# Audio.net
KiCad netlist of a schematic drawn in Altium Designer
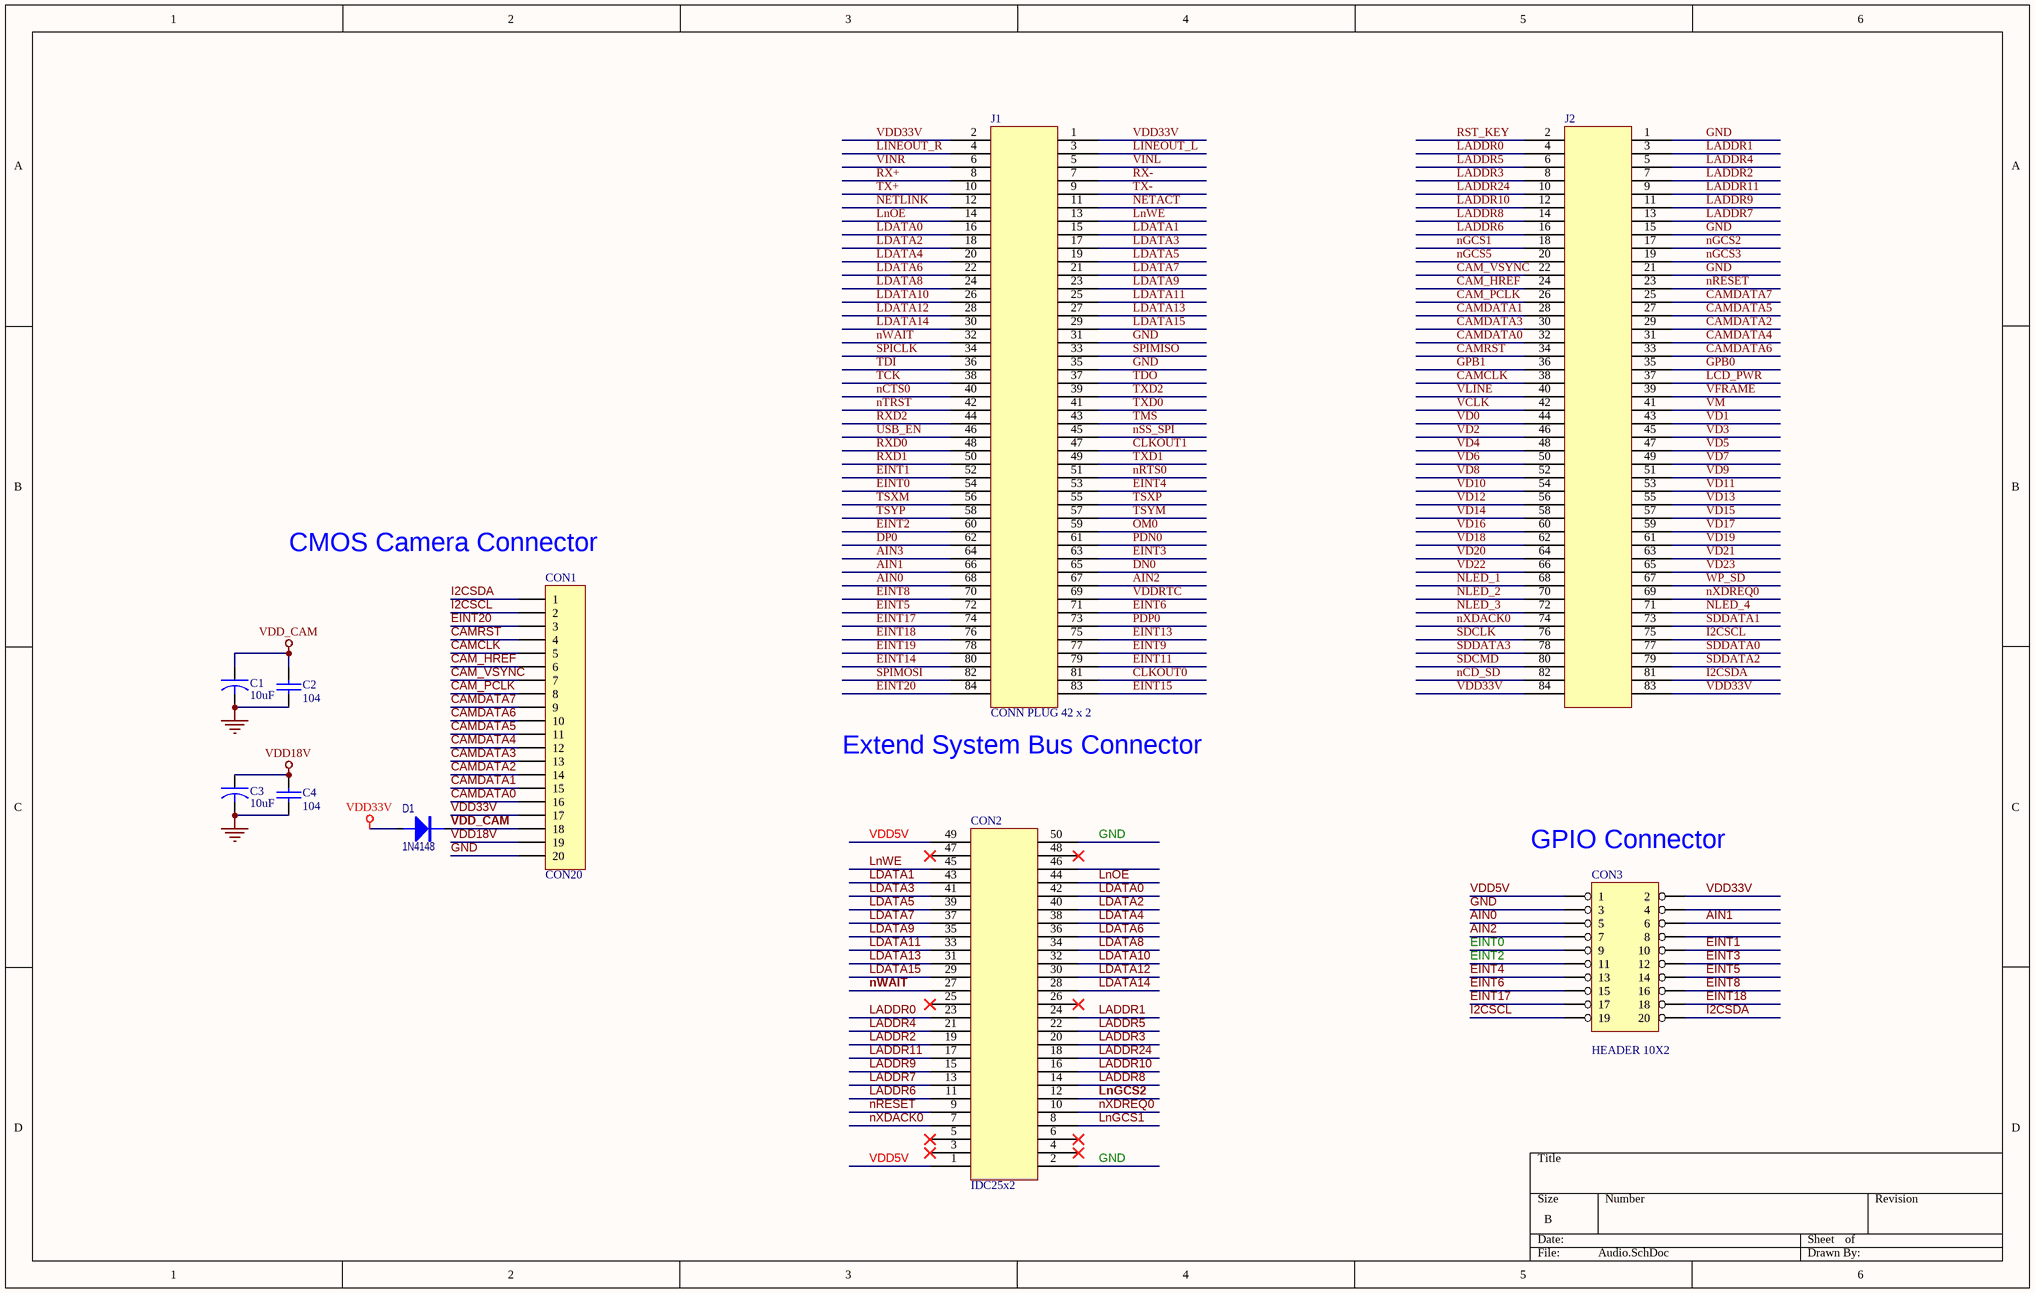
[diagram p0: Audio.SchDoc]

(export (version "E")
  (design (tool "Eeschema 10.0.6"))
  (components
    (comp (ref "C1")
      (value "10uF")
      (footprint "3216A")
      (description "Capacitor")
      (libsource (lib "*") (part "CAPACITOR"))
    )
    (comp (ref "C2")
      (value "104")
      (footprint "0603A")
      (description "Capacitor")
      (libsource (lib "*") (part "CAP"))
    )
    (comp (ref "C3")
      (value "10uF")
      (footprint "3216A")
      (description "Capacitor")
      (libsource (lib "*") (part "CAPACITOR"))
    )
    (comp (ref "C4")
      (value "104")
      (footprint "0603A")
      (description "Capacitor")
      (libsource (lib "*") (part "CAP"))
    )
    (comp (ref "CON1")
      (value "CON20")
      (footprint "IDC20SS")
      (description "Connector")
      (libsource (lib "*") (part "CON20"))
    )
    (comp (ref "CON2") (value "IDC25x2") (footprint "IDC25X2") (libsource (lib "Schlib1") (part "IDC25x2")))
    (comp (ref "CON3") (value "HEADER 10X2") (footprint "IDC20SS") (libsource (lib "*") (part "HEADER 10X2")))
    (comp (ref "D1") (value "1N4148") (footprint "D1206") (libsource (lib "*") (part "DIODE")))
    (comp (ref "J1")
      (value "CONN PLUG 42 x 2")
      (footprint "DIP84")
      (libsource (lib "*") (part "CONN PLUG 42 x 2"))
    )
    (comp (ref "J2")
      (value "CONN PLUG 42 x 2")
      (footprint "DIP84")
      (libsource (lib "*") (part "CONN PLUG 42 x 2"))
    )
  )
  (nets
    (net (code "1") (name "/AIN0") (class "Default")
      (node (ref "CON3") (pin "5") (pinfunction "5_5") (pintype "passive"))
      (node (ref "J1") (pin "68") (pinfunction "68_68") (pintype "passive"))
    )
    (net (code "2") (name "/AIN1") (class "Default")
      (node (ref "CON3") (pin "6") (pinfunction "6_6") (pintype "passive"))
      (node (ref "J1") (pin "66") (pinfunction "66_66") (pintype "passive"))
    )
    (net (code "3") (name "/AIN2") (class "Default")
      (node (ref "CON3") (pin "7") (pinfunction "7_7") (pintype "passive"))
      (node (ref "J1") (pin "67") (pinfunction "67_67") (pintype "passive"))
    )
    (net (code "4") (name "/AIN3") (class "Default")
      (node (ref "J1") (pin "64") (pinfunction "64_64") (pintype "passive"))
    )
    (net (code "5") (name "/CAMCLK") (class "Default")
      (node (ref "CON1") (pin "5") (pinfunction "5_5") (pintype "passive"))
      (node (ref "J2") (pin "38") (pinfunction "38_38") (pintype "passive"))
    )
    (net (code "6") (name "/CAMDATA0") (class "Default")
      (node (ref "CON1") (pin "16") (pinfunction "16_16") (pintype "passive"))
      (node (ref "J2") (pin "32") (pinfunction "32_32") (pintype "passive"))
    )
    (net (code "7") (name "/CAMDATA1") (class "Default")
      (node (ref "CON1") (pin "15") (pinfunction "15_15") (pintype "passive"))
      (node (ref "J2") (pin "28") (pinfunction "28_28") (pintype "passive"))
    )
    (net (code "8") (name "/CAMDATA2") (class "Default")
      (node (ref "CON1") (pin "14") (pinfunction "14_14") (pintype "passive"))
      (node (ref "J2") (pin "29") (pinfunction "29_29") (pintype "passive"))
    )
    (net (code "9") (name "/CAMDATA3") (class "Default")
      (node (ref "CON1") (pin "13") (pinfunction "13_13") (pintype "passive"))
      (node (ref "J2") (pin "30") (pinfunction "30_30") (pintype "passive"))
    )
    (net (code "10") (name "/CAMDATA4") (class "Default")
      (node (ref "CON1") (pin "12") (pinfunction "12_12") (pintype "passive"))
      (node (ref "J2") (pin "31") (pinfunction "31_31") (pintype "passive"))
    )
    (net (code "11") (name "/CAMDATA5") (class "Default")
      (node (ref "CON1") (pin "11") (pinfunction "11_11") (pintype "passive"))
      (node (ref "J2") (pin "27") (pinfunction "27_27") (pintype "passive"))
    )
    (net (code "12") (name "/CAMDATA6") (class "Default")
      (node (ref "CON1") (pin "10") (pinfunction "10_10") (pintype "passive"))
      (node (ref "J2") (pin "33") (pinfunction "33_33") (pintype "passive"))
    )
    (net (code "13") (name "/CAMDATA7") (class "Default")
      (node (ref "CON1") (pin "9") (pinfunction "9_9") (pintype "passive"))
      (node (ref "J2") (pin "25") (pinfunction "25_25") (pintype "passive"))
    )
    (net (code "14") (name "/CAMRST") (class "Default")
      (node (ref "CON1") (pin "4") (pinfunction "4_4") (pintype "passive"))
      (node (ref "J2") (pin "34") (pinfunction "34_34") (pintype "passive"))
    )
    (net (code "15") (name "/CAM_HREF") (class "Default")
      (node (ref "CON1") (pin "6") (pinfunction "6_6") (pintype "passive"))
      (node (ref "J2") (pin "24") (pinfunction "24_24") (pintype "passive"))
    )
    (net (code "16") (name "/CAM_PCLK") (class "Default")
      (node (ref "CON1") (pin "8") (pinfunction "8_8") (pintype "passive"))
      (node (ref "J2") (pin "26") (pinfunction "26_26") (pintype "passive"))
    )
    (net (code "17") (name "/CAM_VSYNC") (class "Default")
      (node (ref "CON1") (pin "7") (pinfunction "7_7") (pintype "passive"))
      (node (ref "J2") (pin "22") (pinfunction "22_22") (pintype "passive"))
    )
    (net (code "18") (name "/CLKOUT0") (class "Default")
      (node (ref "J1") (pin "81") (pinfunction "81_81") (pintype "passive"))
    )
    (net (code "19") (name "/CLKOUT1") (class "Default")
      (node (ref "J1") (pin "47") (pinfunction "47_47") (pintype "passive"))
    )
    (net (code "20") (name "/DN0") (class "Default")
      (node (ref "J1") (pin "65") (pinfunction "65_65") (pintype "passive"))
    )
    (net (code "21") (name "/DP0") (class "Default")
      (node (ref "J1") (pin "62") (pinfunction "62_62") (pintype "passive"))
    )
    (net (code "22") (name "/EINT0") (class "Default")
      (node (ref "CON3") (pin "9") (pinfunction "9_9") (pintype "passive"))
      (node (ref "J1") (pin "54") (pinfunction "54_54") (pintype "passive"))
    )
    (net (code "23") (name "/EINT1") (class "Default")
      (node (ref "CON3") (pin "10") (pinfunction "10_10") (pintype "passive"))
      (node (ref "J1") (pin "52") (pinfunction "52_52") (pintype "passive"))
    )
    (net (code "24") (name "/EINT2") (class "Default")
      (node (ref "CON3") (pin "11") (pinfunction "11_11") (pintype "passive"))
      (node (ref "J1") (pin "60") (pinfunction "60_60") (pintype "passive"))
    )
    (net (code "25") (name "/EINT3") (class "Default")
      (node (ref "CON3") (pin "12") (pinfunction "12_12") (pintype "passive"))
      (node (ref "J1") (pin "63") (pinfunction "63_63") (pintype "passive"))
    )
    (net (code "26") (name "/EINT4") (class "Default")
      (node (ref "CON3") (pin "13") (pinfunction "13_13") (pintype "passive"))
      (node (ref "J1") (pin "53") (pinfunction "53_53") (pintype "passive"))
    )
    (net (code "27") (name "/EINT5") (class "Default")
      (node (ref "CON3") (pin "14") (pinfunction "14_14") (pintype "passive"))
      (node (ref "J1") (pin "72") (pinfunction "72_72") (pintype "passive"))
    )
    (net (code "28") (name "/EINT6") (class "Default")
      (node (ref "CON3") (pin "15") (pinfunction "15_15") (pintype "passive"))
      (node (ref "J1") (pin "71") (pinfunction "71_71") (pintype "passive"))
    )
    (net (code "29") (name "/EINT8") (class "Default")
      (node (ref "CON3") (pin "16") (pinfunction "16_16") (pintype "passive"))
      (node (ref "J1") (pin "70") (pinfunction "70_70") (pintype "passive"))
    )
    (net (code "30") (name "/EINT9") (class "Default")
      (node (ref "J1") (pin "77") (pinfunction "77_77") (pintype "passive"))
    )
    (net (code "31") (name "/EINT11") (class "Default")
      (node (ref "J1") (pin "79") (pinfunction "79_79") (pintype "passive"))
    )
    (net (code "32") (name "/EINT13") (class "Default")
      (node (ref "J1") (pin "75") (pinfunction "75_75") (pintype "passive"))
    )
    (net (code "33") (name "/EINT14") (class "Default")
      (node (ref "J1") (pin "80") (pinfunction "80_80") (pintype "passive"))
    )
    (net (code "34") (name "/EINT15") (class "Default")
      (node (ref "J1") (pin "83") (pinfunction "83_83") (pintype "passive"))
    )
    (net (code "35") (name "/EINT17") (class "Default")
      (node (ref "CON3") (pin "17") (pinfunction "17_17") (pintype "passive"))
      (node (ref "J1") (pin "74") (pinfunction "74_74") (pintype "passive"))
    )
    (net (code "36") (name "/EINT18") (class "Default")
      (node (ref "CON3") (pin "18") (pinfunction "18_18") (pintype "passive"))
      (node (ref "J1") (pin "76") (pinfunction "76_76") (pintype "passive"))
    )
    (net (code "37") (name "/EINT19") (class "Default")
      (node (ref "J1") (pin "78") (pinfunction "78_78") (pintype "passive"))
    )
    (net (code "38") (name "/EINT20") (class "Default")
      (node (ref "CON1") (pin "3") (pinfunction "3_3") (pintype "passive"))
      (node (ref "J1") (pin "84") (pinfunction "84_84") (pintype "passive"))
    )
    (net (code "39") (name "/GPB0") (class "Default")
      (node (ref "J2") (pin "35") (pinfunction "35_35") (pintype "passive"))
    )
    (net (code "40") (name "/GPB1") (class "Default")
      (node (ref "J2") (pin "36") (pinfunction "36_36") (pintype "passive"))
    )
    (net (code "41") (name "/I2CSCL") (class "Default")
      (node (ref "CON1") (pin "2") (pinfunction "2_2") (pintype "passive"))
      (node (ref "CON3") (pin "19") (pinfunction "19_19") (pintype "passive"))
      (node (ref "J2") (pin "75") (pinfunction "75_75") (pintype "passive"))
    )
    (net (code "42") (name "/I2CSDA") (class "Default")
      (node (ref "CON1") (pin "1") (pinfunction "1_1") (pintype "passive"))
      (node (ref "CON3") (pin "20") (pinfunction "20_20") (pintype "passive"))
      (node (ref "J2") (pin "81") (pinfunction "81_81") (pintype "passive"))
    )
    (net (code "43") (name "/LADDR0") (class "Default")
      (node (ref "CON2") (pin "23") (pinfunction "23_23") (pintype "passive"))
      (node (ref "J2") (pin "4") (pinfunction "4_4") (pintype "passive"))
    )
    (net (code "44") (name "/LADDR1") (class "Default")
      (node (ref "CON2") (pin "24") (pinfunction "24_24") (pintype "passive"))
      (node (ref "J2") (pin "3") (pinfunction "3_3") (pintype "passive"))
    )
    (net (code "45") (name "/LADDR2") (class "Default")
      (node (ref "CON2") (pin "19") (pinfunction "19_19") (pintype "passive"))
      (node (ref "J2") (pin "7") (pinfunction "7_7") (pintype "passive"))
    )
    (net (code "46") (name "/LADDR3") (class "Default")
      (node (ref "CON2") (pin "20") (pinfunction "20_20") (pintype "passive"))
      (node (ref "J2") (pin "8") (pinfunction "8_8") (pintype "passive"))
    )
    (net (code "47") (name "/LADDR4") (class "Default")
      (node (ref "CON2") (pin "21") (pinfunction "21_21") (pintype "passive"))
      (node (ref "J2") (pin "5") (pinfunction "5_5") (pintype "passive"))
    )
    (net (code "48") (name "/LADDR5") (class "Default")
      (node (ref "CON2") (pin "22") (pinfunction "22_22") (pintype "passive"))
      (node (ref "J2") (pin "6") (pinfunction "6_6") (pintype "passive"))
    )
    (net (code "49") (name "/LADDR6") (class "Default")
      (node (ref "CON2") (pin "11") (pinfunction "11_11") (pintype "passive"))
      (node (ref "J2") (pin "16") (pinfunction "16_16") (pintype "passive"))
    )
    (net (code "50") (name "/LADDR7") (class "Default")
      (node (ref "CON2") (pin "13") (pinfunction "13_13") (pintype "passive"))
      (node (ref "J2") (pin "13") (pinfunction "13_13") (pintype "passive"))
    )
    (net (code "51") (name "/LADDR8") (class "Default")
      (node (ref "CON2") (pin "14") (pinfunction "14_14") (pintype "passive"))
      (node (ref "J2") (pin "14") (pinfunction "14_14") (pintype "passive"))
    )
    (net (code "52") (name "/LADDR9") (class "Default")
      (node (ref "CON2") (pin "15") (pinfunction "15_15") (pintype "passive"))
      (node (ref "J2") (pin "11") (pinfunction "11_11") (pintype "passive"))
    )
    (net (code "53") (name "/LADDR10") (class "Default")
      (node (ref "CON2") (pin "16") (pinfunction "16_16") (pintype "passive"))
      (node (ref "J2") (pin "12") (pinfunction "12_12") (pintype "passive"))
    )
    (net (code "54") (name "/LADDR11") (class "Default")
      (node (ref "CON2") (pin "17") (pinfunction "17_17") (pintype "passive"))
      (node (ref "J2") (pin "9") (pinfunction "9_9") (pintype "passive"))
    )
    (net (code "55") (name "/LADDR24") (class "Default")
      (node (ref "CON2") (pin "18") (pinfunction "18_18") (pintype "passive"))
      (node (ref "J2") (pin "10") (pinfunction "10_10") (pintype "passive"))
    )
    (net (code "56") (name "/LCD_PWR") (class "Default")
      (node (ref "J2") (pin "37") (pinfunction "37_37") (pintype "passive"))
    )
    (net (code "57") (name "/LDATA0") (class "Default")
      (node (ref "CON2") (pin "42") (pinfunction "42_42") (pintype "passive"))
      (node (ref "J1") (pin "16") (pinfunction "16_16") (pintype "passive"))
    )
    (net (code "58") (name "/LDATA1") (class "Default")
      (node (ref "CON2") (pin "43") (pinfunction "43_43") (pintype "passive"))
      (node (ref "J1") (pin "15") (pinfunction "15_15") (pintype "passive"))
    )
    (net (code "59") (name "/LDATA2") (class "Default")
      (node (ref "CON2") (pin "40") (pinfunction "40_40") (pintype "passive"))
      (node (ref "J1") (pin "18") (pinfunction "18_18") (pintype "passive"))
    )
    (net (code "60") (name "/LDATA3") (class "Default")
      (node (ref "CON2") (pin "41") (pinfunction "41_41") (pintype "passive"))
      (node (ref "J1") (pin "17") (pinfunction "17_17") (pintype "passive"))
    )
    (net (code "61") (name "/LDATA4") (class "Default")
      (node (ref "CON2") (pin "38") (pinfunction "38_38") (pintype "passive"))
      (node (ref "J1") (pin "20") (pinfunction "20_20") (pintype "passive"))
    )
    (net (code "62") (name "/LDATA5") (class "Default")
      (node (ref "CON2") (pin "39") (pinfunction "39_39") (pintype "passive"))
      (node (ref "J1") (pin "19") (pinfunction "19_19") (pintype "passive"))
    )
    (net (code "63") (name "/LDATA6") (class "Default")
      (node (ref "CON2") (pin "36") (pinfunction "36_36") (pintype "passive"))
      (node (ref "J1") (pin "22") (pinfunction "22_22") (pintype "passive"))
    )
    (net (code "64") (name "/LDATA7") (class "Default")
      (node (ref "CON2") (pin "37") (pinfunction "37_37") (pintype "passive"))
      (node (ref "J1") (pin "21") (pinfunction "21_21") (pintype "passive"))
    )
    (net (code "65") (name "/LDATA8") (class "Default")
      (node (ref "CON2") (pin "34") (pinfunction "34_34") (pintype "passive"))
      (node (ref "J1") (pin "24") (pinfunction "24_24") (pintype "passive"))
    )
    (net (code "66") (name "/LDATA9") (class "Default")
      (node (ref "CON2") (pin "35") (pinfunction "35_35") (pintype "passive"))
      (node (ref "J1") (pin "23") (pinfunction "23_23") (pintype "passive"))
    )
    (net (code "67") (name "/LDATA10") (class "Default")
      (node (ref "CON2") (pin "32") (pinfunction "32_32") (pintype "passive"))
      (node (ref "J1") (pin "26") (pinfunction "26_26") (pintype "passive"))
    )
    (net (code "68") (name "/LDATA11") (class "Default")
      (node (ref "CON2") (pin "33") (pinfunction "33_33") (pintype "passive"))
      (node (ref "J1") (pin "25") (pinfunction "25_25") (pintype "passive"))
    )
    (net (code "69") (name "/LDATA12") (class "Default")
      (node (ref "CON2") (pin "30") (pinfunction "30_30") (pintype "passive"))
      (node (ref "J1") (pin "28") (pinfunction "28_28") (pintype "passive"))
    )
    (net (code "70") (name "/LDATA13") (class "Default")
      (node (ref "CON2") (pin "31") (pinfunction "31_31") (pintype "passive"))
      (node (ref "J1") (pin "27") (pinfunction "27_27") (pintype "passive"))
    )
    (net (code "71") (name "/LDATA14") (class "Default")
      (node (ref "CON2") (pin "28") (pinfunction "28_28") (pintype "passive"))
      (node (ref "J1") (pin "30") (pinfunction "30_30") (pintype "passive"))
    )
    (net (code "72") (name "/LDATA15") (class "Default")
      (node (ref "CON2") (pin "29") (pinfunction "29_29") (pintype "passive"))
      (node (ref "J1") (pin "29") (pinfunction "29_29") (pintype "passive"))
    )
    (net (code "73") (name "/LINEOUT_L") (class "Default")
      (node (ref "J1") (pin "3") (pinfunction "3_3") (pintype "passive"))
    )
    (net (code "74") (name "/LINEOUT_R") (class "Default")
      (node (ref "J1") (pin "4") (pinfunction "4_4") (pintype "passive"))
    )
    (net (code "75") (name "/LnGCS1") (class "Default")
      (node (ref "CON2") (pin "8") (pinfunction "8_8") (pintype "passive"))
    )
    (net (code "76") (name "/LnGCS2") (class "Default")
      (node (ref "CON2") (pin "12") (pinfunction "12_12") (pintype "passive"))
    )
    (net (code "77") (name "/LnOE") (class "Default")
      (node (ref "CON2") (pin "44") (pinfunction "44_44") (pintype "passive"))
      (node (ref "J1") (pin "14") (pinfunction "14_14") (pintype "passive"))
    )
    (net (code "78") (name "/LnWE") (class "Default")
      (node (ref "CON2") (pin "45") (pinfunction "45_45") (pintype "passive"))
      (node (ref "J1") (pin "13") (pinfunction "13_13") (pintype "passive"))
    )
    (net (code "79") (name "/NETACT") (class "Default")
      (node (ref "J1") (pin "11") (pinfunction "11_11") (pintype "passive"))
    )
    (net (code "80") (name "/NETLINK") (class "Default")
      (node (ref "J1") (pin "12") (pinfunction "12_12") (pintype "passive"))
    )
    (net (code "81") (name "/NLED_1") (class "Default")
      (node (ref "J2") (pin "68") (pinfunction "68_68") (pintype "passive"))
    )
    (net (code "82") (name "/NLED_2") (class "Default")
      (node (ref "J2") (pin "70") (pinfunction "70_70") (pintype "passive"))
    )
    (net (code "83") (name "/NLED_3") (class "Default")
      (node (ref "J2") (pin "72") (pinfunction "72_72") (pintype "passive"))
    )
    (net (code "84") (name "/NLED_4") (class "Default")
      (node (ref "J2") (pin "71") (pinfunction "71_71") (pintype "passive"))
    )
    (net (code "85") (name "/OM0") (class "Default")
      (node (ref "J1") (pin "59") (pinfunction "59_59") (pintype "passive"))
    )
    (net (code "86") (name "/PDN0") (class "Default")
      (node (ref "J1") (pin "61") (pinfunction "61_61") (pintype "passive"))
    )
    (net (code "87") (name "/PDP0") (class "Default")
      (node (ref "J1") (pin "73") (pinfunction "73_73") (pintype "passive"))
    )
    (net (code "88") (name "/RST_KEY") (class "Default")
      (node (ref "J2") (pin "2") (pinfunction "2_2") (pintype "passive"))
    )
    (net (code "89") (name "/RX+") (class "Default")
      (node (ref "J1") (pin "8") (pinfunction "8_8") (pintype "passive"))
    )
    (net (code "90") (name "/RX-") (class "Default")
      (node (ref "J1") (pin "7") (pinfunction "7_7") (pintype "passive"))
    )
    (net (code "91") (name "/RXD0") (class "Default")
      (node (ref "J1") (pin "48") (pinfunction "48_48") (pintype "passive"))
    )
    (net (code "92") (name "/RXD1") (class "Default")
      (node (ref "J1") (pin "50") (pinfunction "50_50") (pintype "passive"))
    )
    (net (code "93") (name "/RXD2") (class "Default")
      (node (ref "J1") (pin "44") (pinfunction "44_44") (pintype "passive"))
    )
    (net (code "94") (name "/SDCLK") (class "Default")
      (node (ref "J2") (pin "76") (pinfunction "76_76") (pintype "passive"))
    )
    (net (code "95") (name "/SDCMD") (class "Default")
      (node (ref "J2") (pin "80") (pinfunction "80_80") (pintype "passive"))
    )
    (net (code "96") (name "/SDDATA0") (class "Default")
      (node (ref "J2") (pin "77") (pinfunction "77_77") (pintype "passive"))
    )
    (net (code "97") (name "/SDDATA1") (class "Default")
      (node (ref "J2") (pin "73") (pinfunction "73_73") (pintype "passive"))
    )
    (net (code "98") (name "/SDDATA2") (class "Default")
      (node (ref "J2") (pin "79") (pinfunction "79_79") (pintype "passive"))
    )
    (net (code "99") (name "/SDDATA3") (class "Default")
      (node (ref "J2") (pin "78") (pinfunction "78_78") (pintype "passive"))
    )
    (net (code "100") (name "/SPICLK") (class "Default")
      (node (ref "J1") (pin "34") (pinfunction "34_34") (pintype "passive"))
    )
    (net (code "101") (name "/SPIMISO") (class "Default")
      (node (ref "J1") (pin "33") (pinfunction "33_33") (pintype "passive"))
    )
    (net (code "102") (name "/SPIMOSI") (class "Default")
      (node (ref "J1") (pin "82") (pinfunction "82_82") (pintype "passive"))
    )
    (net (code "103") (name "/TCK") (class "Default")
      (node (ref "J1") (pin "38") (pinfunction "38_38") (pintype "passive"))
    )
    (net (code "104") (name "/TDI") (class "Default")
      (node (ref "J1") (pin "36") (pinfunction "36_36") (pintype "passive"))
    )
    (net (code "105") (name "/TDO") (class "Default")
      (node (ref "J1") (pin "37") (pinfunction "37_37") (pintype "passive"))
    )
    (net (code "106") (name "/TMS") (class "Default")
      (node (ref "J1") (pin "43") (pinfunction "43_43") (pintype "passive"))
    )
    (net (code "107") (name "/TSXM") (class "Default")
      (node (ref "J1") (pin "56") (pinfunction "56_56") (pintype "passive"))
    )
    (net (code "108") (name "/TSXP") (class "Default")
      (node (ref "J1") (pin "55") (pinfunction "55_55") (pintype "passive"))
    )
    (net (code "109") (name "/TSYM") (class "Default")
      (node (ref "J1") (pin "57") (pinfunction "57_57") (pintype "passive"))
    )
    (net (code "110") (name "/TSYP") (class "Default")
      (node (ref "J1") (pin "58") (pinfunction "58_58") (pintype "passive"))
    )
    (net (code "111") (name "/TX+") (class "Default")
      (node (ref "J1") (pin "10") (pinfunction "10_10") (pintype "passive"))
    )
    (net (code "112") (name "/TX-") (class "Default")
      (node (ref "J1") (pin "9") (pinfunction "9_9") (pintype "passive"))
    )
    (net (code "113") (name "/TXD0") (class "Default")
      (node (ref "J1") (pin "41") (pinfunction "41_41") (pintype "passive"))
    )
    (net (code "114") (name "/TXD1") (class "Default")
      (node (ref "J1") (pin "49") (pinfunction "49_49") (pintype "passive"))
    )
    (net (code "115") (name "/TXD2") (class "Default")
      (node (ref "J1") (pin "39") (pinfunction "39_39") (pintype "passive"))
    )
    (net (code "116") (name "/USB_EN") (class "Default")
      (node (ref "J1") (pin "46") (pinfunction "46_46") (pintype "passive"))
    )
    (net (code "117") (name "/VCLK") (class "Default")
      (node (ref "J2") (pin "42") (pinfunction "42_42") (pintype "passive"))
    )
    (net (code "118") (name "/VD0") (class "Default")
      (node (ref "J2") (pin "44") (pinfunction "44_44") (pintype "passive"))
    )
    (net (code "119") (name "/VD1") (class "Default")
      (node (ref "J2") (pin "43") (pinfunction "43_43") (pintype "passive"))
    )
    (net (code "120") (name "/VD2") (class "Default")
      (node (ref "J2") (pin "46") (pinfunction "46_46") (pintype "passive"))
    )
    (net (code "121") (name "/VD3") (class "Default")
      (node (ref "J2") (pin "45") (pinfunction "45_45") (pintype "passive"))
    )
    (net (code "122") (name "/VD4") (class "Default")
      (node (ref "J2") (pin "48") (pinfunction "48_48") (pintype "passive"))
    )
    (net (code "123") (name "/VD5") (class "Default")
      (node (ref "J2") (pin "47") (pinfunction "47_47") (pintype "passive"))
    )
    (net (code "124") (name "/VD6") (class "Default")
      (node (ref "J2") (pin "50") (pinfunction "50_50") (pintype "passive"))
    )
    (net (code "125") (name "/VD7") (class "Default")
      (node (ref "J2") (pin "49") (pinfunction "49_49") (pintype "passive"))
    )
    (net (code "126") (name "/VD8") (class "Default")
      (node (ref "J2") (pin "52") (pinfunction "52_52") (pintype "passive"))
    )
    (net (code "127") (name "/VD9") (class "Default")
      (node (ref "J2") (pin "51") (pinfunction "51_51") (pintype "passive"))
    )
    (net (code "128") (name "/VD10") (class "Default")
      (node (ref "J2") (pin "54") (pinfunction "54_54") (pintype "passive"))
    )
    (net (code "129") (name "/VD11") (class "Default")
      (node (ref "J2") (pin "53") (pinfunction "53_53") (pintype "passive"))
    )
    (net (code "130") (name "/VD12") (class "Default")
      (node (ref "J2") (pin "56") (pinfunction "56_56") (pintype "passive"))
    )
    (net (code "131") (name "/VD13") (class "Default")
      (node (ref "J2") (pin "55") (pinfunction "55_55") (pintype "passive"))
    )
    (net (code "132") (name "/VD14") (class "Default")
      (node (ref "J2") (pin "58") (pinfunction "58_58") (pintype "passive"))
    )
    (net (code "133") (name "/VD15") (class "Default")
      (node (ref "J2") (pin "57") (pinfunction "57_57") (pintype "passive"))
    )
    (net (code "134") (name "/VD16") (class "Default")
      (node (ref "J2") (pin "60") (pinfunction "60_60") (pintype "passive"))
    )
    (net (code "135") (name "/VD17") (class "Default")
      (node (ref "J2") (pin "59") (pinfunction "59_59") (pintype "passive"))
    )
    (net (code "136") (name "/VD18") (class "Default")
      (node (ref "J2") (pin "62") (pinfunction "62_62") (pintype "passive"))
    )
    (net (code "137") (name "/VD19") (class "Default")
      (node (ref "J2") (pin "61") (pinfunction "61_61") (pintype "passive"))
    )
    (net (code "138") (name "/VD20") (class "Default")
      (node (ref "J2") (pin "64") (pinfunction "64_64") (pintype "passive"))
    )
    (net (code "139") (name "/VD21") (class "Default")
      (node (ref "J2") (pin "63") (pinfunction "63_63") (pintype "passive"))
    )
    (net (code "140") (name "/VD22") (class "Default")
      (node (ref "J2") (pin "66") (pinfunction "66_66") (pintype "passive"))
    )
    (net (code "141") (name "/VD23") (class "Default")
      (node (ref "J2") (pin "65") (pinfunction "65_65") (pintype "passive"))
    )
    (net (code "142") (name "/VDD5V") (class "Default")
      (node (ref "CON2") (pin "1") (pinfunction "1_1") (pintype "passive"))
      (node (ref "CON2") (pin "49") (pinfunction "49_49") (pintype "passive"))
      (node (ref "CON3") (pin "1") (pinfunction "1_1") (pintype "passive"))
    )
    (net (code "143") (name "/VDDRTC") (class "Default")
      (node (ref "J1") (pin "69") (pinfunction "69_69") (pintype "passive"))
    )
    (net (code "144") (name "/VFRAME") (class "Default")
      (node (ref "J2") (pin "39") (pinfunction "39_39") (pintype "passive"))
    )
    (net (code "145") (name "/VINL") (class "Default")
      (node (ref "J1") (pin "5") (pinfunction "5_5") (pintype "passive"))
    )
    (net (code "146") (name "/VINR") (class "Default")
      (node (ref "J1") (pin "6") (pinfunction "6_6") (pintype "passive"))
    )
    (net (code "147") (name "/VLINE") (class "Default")
      (node (ref "J2") (pin "40") (pinfunction "40_40") (pintype "passive"))
    )
    (net (code "148") (name "/VM") (class "Default")
      (node (ref "J2") (pin "41") (pinfunction "41_41") (pintype "passive"))
    )
    (net (code "149") (name "/WP_SD") (class "Default")
      (node (ref "J2") (pin "67") (pinfunction "67_67") (pintype "passive"))
    )
    (net (code "150") (name "/nCD_SD") (class "Default")
      (node (ref "J2") (pin "82") (pinfunction "82_82") (pintype "passive"))
    )
    (net (code "151") (name "/nCTS0") (class "Default")
      (node (ref "J1") (pin "40") (pinfunction "40_40") (pintype "passive"))
    )
    (net (code "152") (name "/nGCS1") (class "Default")
      (node (ref "J2") (pin "18") (pinfunction "18_18") (pintype "passive"))
    )
    (net (code "153") (name "/nGCS2") (class "Default")
      (node (ref "J2") (pin "17") (pinfunction "17_17") (pintype "passive"))
    )
    (net (code "154") (name "/nGCS3") (class "Default")
      (node (ref "J2") (pin "19") (pinfunction "19_19") (pintype "passive"))
    )
    (net (code "155") (name "/nGCS5") (class "Default")
      (node (ref "J2") (pin "20") (pinfunction "20_20") (pintype "passive"))
    )
    (net (code "156") (name "/nRESET") (class "Default")
      (node (ref "CON2") (pin "9") (pinfunction "9_9") (pintype "passive"))
      (node (ref "J2") (pin "23") (pinfunction "23_23") (pintype "passive"))
    )
    (net (code "157") (name "/nRTS0") (class "Default")
      (node (ref "J1") (pin "51") (pinfunction "51_51") (pintype "passive"))
    )
    (net (code "158") (name "/nSS_SPI") (class "Default")
      (node (ref "J1") (pin "45") (pinfunction "45_45") (pintype "passive"))
    )
    (net (code "159") (name "/nTRST") (class "Default")
      (node (ref "J1") (pin "42") (pinfunction "42_42") (pintype "passive"))
    )
    (net (code "160") (name "/nWAIT") (class "Default")
      (node (ref "CON2") (pin "27") (pinfunction "27_27") (pintype "passive"))
      (node (ref "J1") (pin "32") (pinfunction "32_32") (pintype "passive"))
    )
    (net (code "161") (name "/nXDACK0") (class "Default")
      (node (ref "CON2") (pin "7") (pinfunction "7_7") (pintype "passive"))
      (node (ref "J2") (pin "74") (pinfunction "74_74") (pintype "passive"))
    )
    (net (code "162") (name "/nXDREQ0") (class "Default")
      (node (ref "CON2") (pin "10") (pinfunction "10_10") (pintype "passive"))
      (node (ref "J2") (pin "69") (pinfunction "69_69") (pintype "passive"))
    )
    (net (code "163") (name "GND") (class "Default")
      (node (ref "C1") (pin "2") (pinfunction "2_2") (pintype "passive"))
      (node (ref "C2") (pin "2") (pinfunction "2_2") (pintype "passive"))
      (node (ref "C3") (pin "2") (pinfunction "2_2") (pintype "passive"))
      (node (ref "C4") (pin "2") (pinfunction "2_2") (pintype "passive"))
      (node (ref "CON1") (pin "20") (pinfunction "20_20") (pintype "passive"))
      (node (ref "CON2") (pin "2") (pinfunction "2_2") (pintype "passive"))
      (node (ref "CON2") (pin "50") (pinfunction "50_50") (pintype "passive"))
      (node (ref "CON3") (pin "3") (pinfunction "3_3") (pintype "passive"))
      (node (ref "J1") (pin "31") (pinfunction "31_31") (pintype "passive"))
      (node (ref "J1") (pin "35") (pinfunction "35_35") (pintype "passive"))
      (node (ref "J2") (pin "1") (pinfunction "1_1") (pintype "passive"))
      (node (ref "J2") (pin "15") (pinfunction "15_15") (pintype "passive"))
      (node (ref "J2") (pin "21") (pinfunction "21_21") (pintype "passive"))
    )
    (net (code "164") (name "VDD18V") (class "Default")
      (node (ref "C3") (pin "1") (pinfunction "1_1") (pintype "passive"))
      (node (ref "C4") (pin "1") (pinfunction "1_1") (pintype "passive"))
      (node (ref "CON1") (pin "19") (pinfunction "19_19") (pintype "passive"))
    )
    (net (code "165") (name "VDD33V") (class "Default")
      (node (ref "CON1") (pin "17") (pinfunction "17_17") (pintype "passive"))
      (node (ref "CON3") (pin "2") (pinfunction "2_2") (pintype "passive"))
      (node (ref "D1") (pin "1") (pinfunction "1_1") (pintype "passive"))
      (node (ref "J1") (pin "1") (pinfunction "1_1") (pintype "passive"))
      (node (ref "J1") (pin "2") (pinfunction "2_2") (pintype "passive"))
      (node (ref "J2") (pin "83") (pinfunction "83_83") (pintype "passive"))
      (node (ref "J2") (pin "84") (pinfunction "84_84") (pintype "passive"))
    )
    (net (code "166") (name "VDD_CAM") (class "Default")
      (node (ref "C1") (pin "1") (pinfunction "1_1") (pintype "passive"))
      (node (ref "C2") (pin "1") (pinfunction "1_1") (pintype "passive"))
      (node (ref "CON1") (pin "18") (pinfunction "18_18") (pintype "passive"))
      (node (ref "D1") (pin "2") (pinfunction "2_2") (pintype "passive"))
    )
    (net (code "167") (name "unconnected-(CON2-Pad3)") (class "Default")
      (node (ref "CON2") (pin "3") (pinfunction "3_3") (pintype "passive+no_connect"))
    )
    (net (code "168") (name "unconnected-(CON2-Pad4)") (class "Default")
      (node (ref "CON2") (pin "4") (pinfunction "4_4") (pintype "passive+no_connect"))
    )
    (net (code "169") (name "unconnected-(CON2-Pad5)") (class "Default")
      (node (ref "CON2") (pin "5") (pinfunction "5_5") (pintype "passive+no_connect"))
    )
    (net (code "170") (name "unconnected-(CON2-Pad6)") (class "Default")
      (node (ref "CON2") (pin "6") (pinfunction "6_6") (pintype "passive+no_connect"))
    )
    (net (code "171") (name "unconnected-(CON2-Pad25)") (class "Default")
      (node (ref "CON2") (pin "25") (pinfunction "25_25") (pintype "passive+no_connect"))
    )
    (net (code "172") (name "unconnected-(CON2-Pad26)") (class "Default")
      (node (ref "CON2") (pin "26") (pinfunction "26_26") (pintype "passive+no_connect"))
    )
    (net (code "173") (name "unconnected-(CON2-Pad46)") (class "Default")
      (node (ref "CON2") (pin "46") (pinfunction "46_46") (pintype "passive"))
    )
    (net (code "174") (name "unconnected-(CON2-Pad47)") (class "Default")
      (node (ref "CON2") (pin "47") (pinfunction "47_47") (pintype "passive+no_connect"))
    )
    (net (code "175") (name "unconnected-(CON2-Pad48)") (class "Default")
      (node (ref "CON2") (pin "48") (pinfunction "48_48") (pintype "passive+no_connect"))
    )
    (net (code "176") (name "unconnected-(CON3-Pad4)") (class "Default")
      (node (ref "CON3") (pin "4") (pinfunction "4_4") (pintype "passive"))
    )
    (net (code "177") (name "unconnected-(CON3-Pad8)") (class "Default")
      (node (ref "CON3") (pin "8") (pinfunction "8_8") (pintype "passive"))
    )
  )
)
